# USBC.net
KiCad netlist of a schematic drawn in Altium Designer
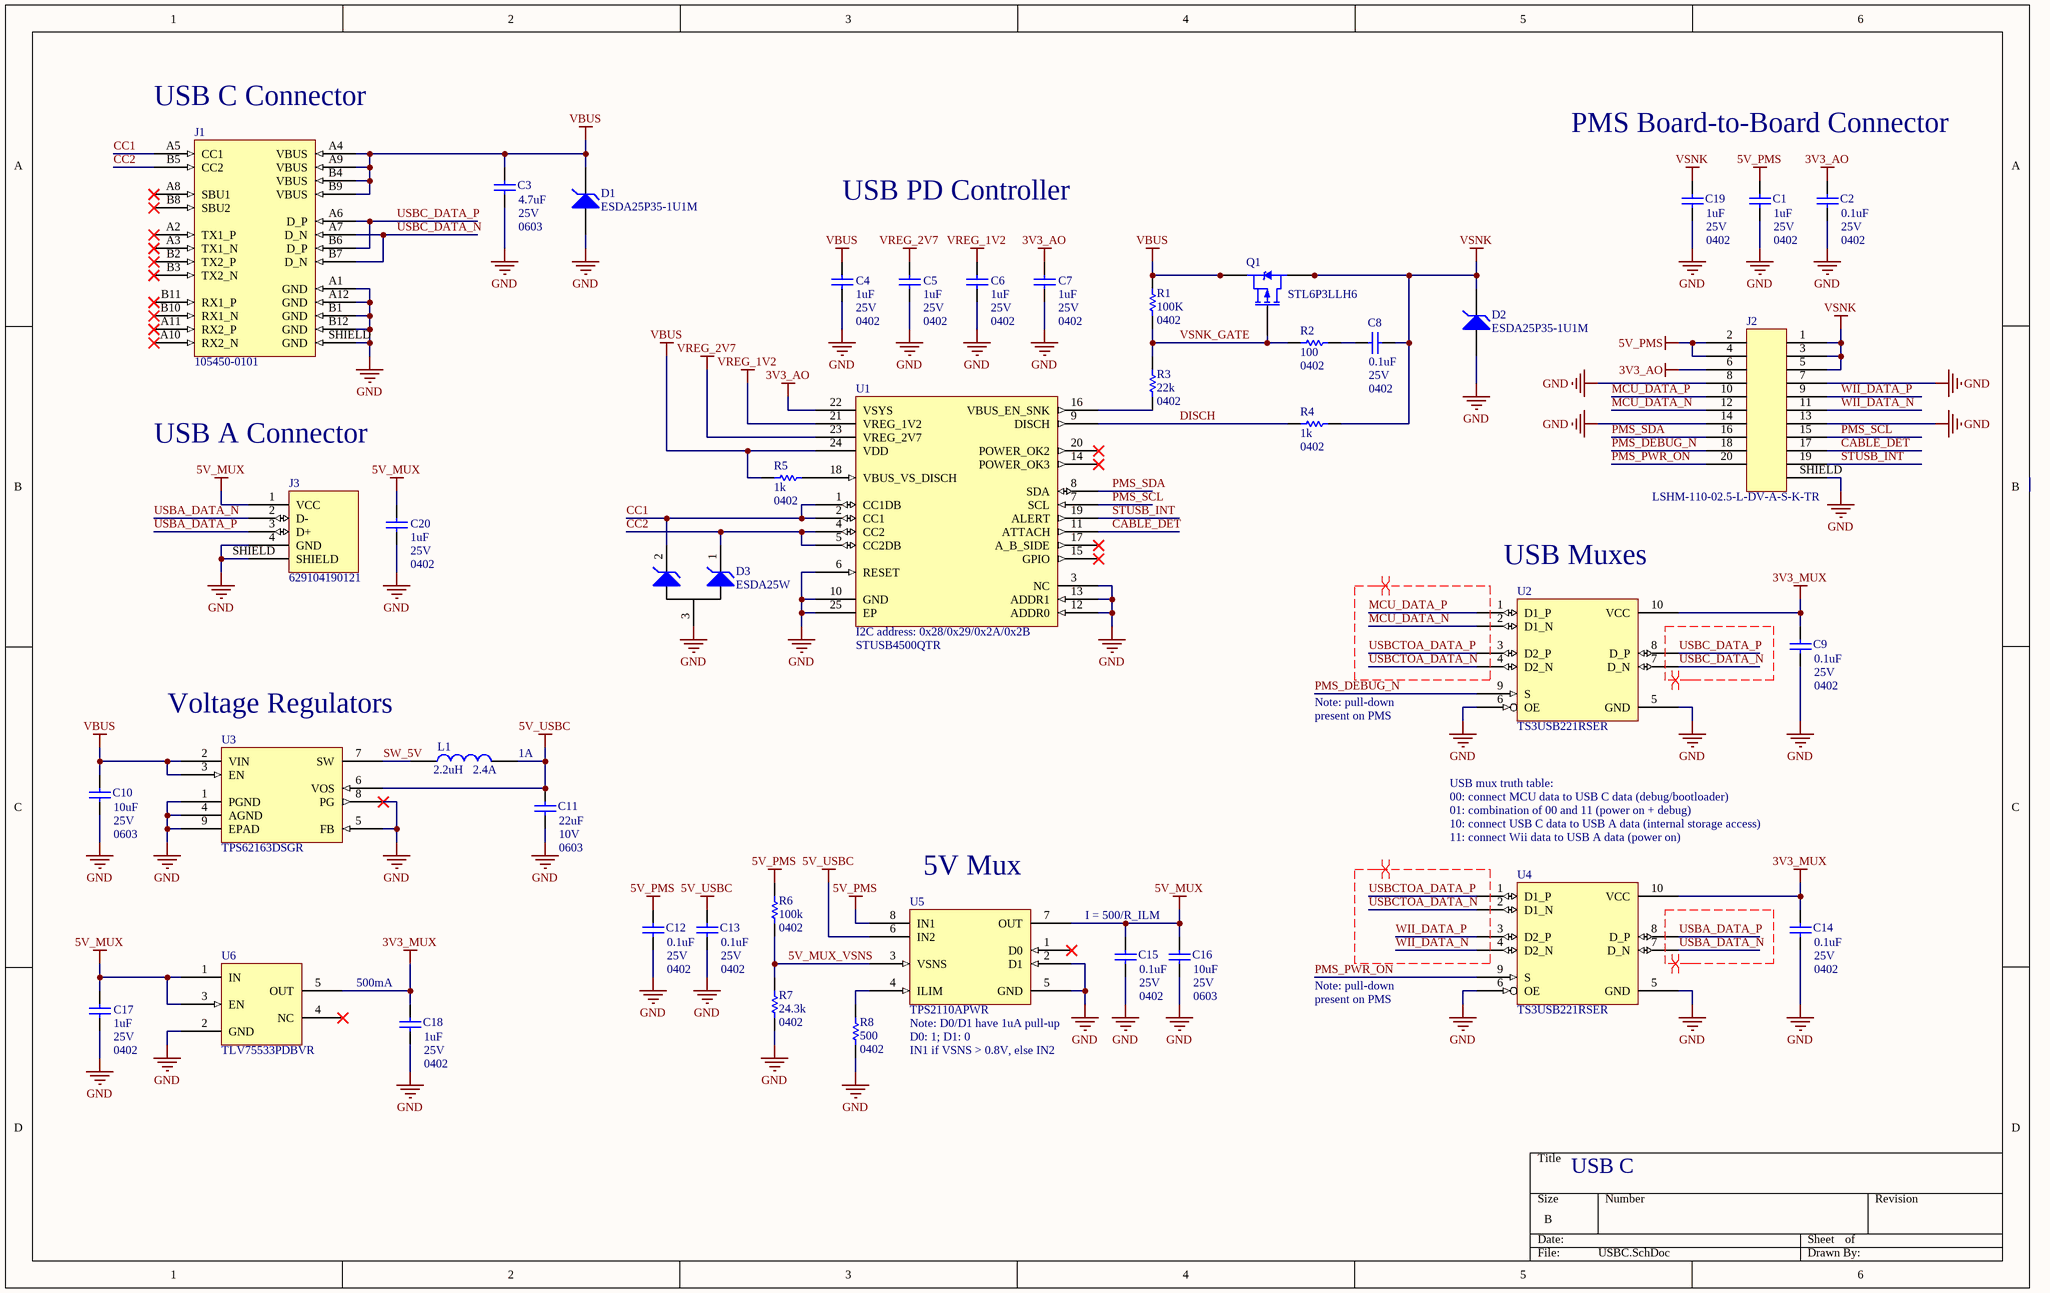
[diagram p0: USBC.SchDoc]

(export (version "E")
  (design (tool "Eeschema 10.0.6"))
  (components
    (comp (ref "C1")
      (value "1uF")
      (footprint "CAPC1005X06N")
      (description "General purpose capacitor")
      (fields
        (field (name "RATED VOLTAGE") "25V")
        (field (name "PACKAGE") "0402")
        (field (name "Comment") "Capacitor")
      )
      (libsource (lib "Schematic_Generic") (part "Capacitor"))
    )
    (comp (ref "C2")
      (value "0.1uF")
      (footprint "CAPC1005X06N")
      (description "General purpose capacitor")
      (fields
        (field (name "RATED VOLTAGE") "25V")
        (field (name "PACKAGE") "0402")
        (field (name "Comment") "Capacitor")
      )
      (libsource (lib "Schematic_Generic") (part "Capacitor"))
    )
    (comp (ref "C3")
      (value "4.7uF")
      (footprint "CAPC1608X09N")
      (description "General purpose capacitor")
      (fields
        (field (name "RATED VOLTAGE") "25V")
        (field (name "PACKAGE") "0603")
        (field (name "Comment") "Capacitor")
      )
      (libsource (lib "Schematic_Generic") (part "Capacitor"))
    )
    (comp (ref "C4")
      (value "1uF")
      (footprint "CAPC1005X06N")
      (description "General purpose capacitor")
      (fields
        (field (name "RATED VOLTAGE") "25V")
        (field (name "PACKAGE") "0402")
        (field (name "Comment") "Capacitor")
      )
      (libsource (lib "Schematic_Generic") (part "Capacitor"))
    )
    (comp (ref "C5")
      (value "1uF")
      (footprint "CAPC1005X06N")
      (description "General purpose capacitor")
      (fields
        (field (name "RATED VOLTAGE") "25V")
        (field (name "PACKAGE") "0402")
        (field (name "Comment") "Capacitor")
      )
      (libsource (lib "Schematic_Generic") (part "Capacitor"))
    )
    (comp (ref "C6")
      (value "1uF")
      (footprint "CAPC1005X06N")
      (description "General purpose capacitor")
      (fields
        (field (name "RATED VOLTAGE") "25V")
        (field (name "PACKAGE") "0402")
        (field (name "Comment") "Capacitor")
      )
      (libsource (lib "Schematic_Generic") (part "Capacitor"))
    )
    (comp (ref "C7")
      (value "1uF")
      (footprint "CAPC1005X06N")
      (description "General purpose capacitor")
      (fields
        (field (name "RATED VOLTAGE") "25V")
        (field (name "PACKAGE") "0402")
        (field (name "Comment") "Capacitor")
      )
      (libsource (lib "Schematic_Generic") (part "Capacitor"))
    )
    (comp (ref "C8")
      (value "0.1uF")
      (footprint "CAPC1005X06N")
      (description "General purpose capacitor")
      (fields
        (field (name "RATED VOLTAGE") "25V")
        (field (name "PACKAGE") "0402")
        (field (name "Comment") "Capacitor")
      )
      (libsource (lib "Schematic_Generic") (part "Capacitor"))
    )
    (comp (ref "C9")
      (value "0.1uF")
      (footprint "CAPC1005X06N")
      (description "General purpose capacitor")
      (fields
        (field (name "RATED VOLTAGE") "25V")
        (field (name "PACKAGE") "0402")
        (field (name "Comment") "Capacitor")
      )
      (libsource (lib "Schematic_Generic") (part "Capacitor"))
    )
    (comp (ref "C10")
      (value "10uF")
      (footprint "CAPC1608X09N")
      (description "General purpose capacitor")
      (fields
        (field (name "RATED VOLTAGE") "25V")
        (field (name "PACKAGE") "0603")
        (field (name "Comment") "Capacitor")
      )
      (libsource (lib "Schematic_Generic") (part "Capacitor"))
    )
    (comp (ref "C11")
      (value "22uF")
      (footprint "CAPC1608X09N")
      (description "General purpose capacitor")
      (fields
        (field (name "RATED VOLTAGE") "10V")
        (field (name "PACKAGE") "0603")
        (field (name "Comment") "Capacitor")
      )
      (libsource (lib "Schematic_Generic") (part "Capacitor"))
    )
    (comp (ref "C12")
      (value "0.1uF")
      (footprint "CAPC1005X06N")
      (description "General purpose capacitor")
      (fields
        (field (name "RATED VOLTAGE") "25V")
        (field (name "PACKAGE") "0402")
        (field (name "Comment") "Capacitor")
      )
      (libsource (lib "Schematic_Generic") (part "Capacitor"))
    )
    (comp (ref "C13")
      (value "0.1uF")
      (footprint "CAPC1005X06N")
      (description "General purpose capacitor")
      (fields
        (field (name "RATED VOLTAGE") "25V")
        (field (name "PACKAGE") "0402")
        (field (name "Comment") "Capacitor")
      )
      (libsource (lib "Schematic_Generic") (part "Capacitor"))
    )
    (comp (ref "C14")
      (value "0.1uF")
      (footprint "CAPC1005X06N")
      (description "General purpose capacitor")
      (fields
        (field (name "RATED VOLTAGE") "25V")
        (field (name "PACKAGE") "0402")
        (field (name "Comment") "Capacitor")
      )
      (libsource (lib "Schematic_Generic") (part "Capacitor"))
    )
    (comp (ref "C15")
      (value "0.1uF")
      (footprint "CAPC1005X06N")
      (description "General purpose capacitor")
      (fields
        (field (name "RATED VOLTAGE") "25V")
        (field (name "PACKAGE") "0402")
        (field (name "Comment") "Capacitor")
      )
      (libsource (lib "Schematic_Generic") (part "Capacitor"))
    )
    (comp (ref "C16")
      (value "10uF")
      (footprint "CAPC1608X09N")
      (description "General purpose capacitor")
      (fields
        (field (name "RATED VOLTAGE") "25V")
        (field (name "PACKAGE") "0603")
        (field (name "Comment") "Capacitor")
      )
      (libsource (lib "Schematic_Generic") (part "Capacitor"))
    )
    (comp (ref "C17")
      (value "1uF")
      (footprint "CAPC1005X06N")
      (description "General purpose capacitor")
      (fields
        (field (name "RATED VOLTAGE") "25V")
        (field (name "PACKAGE") "0402")
        (field (name "Comment") "Capacitor")
      )
      (libsource (lib "Schematic_Generic") (part "Capacitor"))
    )
    (comp (ref "C18")
      (value "1uF")
      (footprint "CAPC1005X06N")
      (description "General purpose capacitor")
      (fields
        (field (name "RATED VOLTAGE") "25V")
        (field (name "PACKAGE") "0402")
        (field (name "Comment") "Capacitor")
      )
      (libsource (lib "Schematic_Generic") (part "Capacitor"))
    )
    (comp (ref "C19")
      (value "1uF")
      (footprint "CAPC1005X06N")
      (description "General purpose capacitor")
      (fields
        (field (name "RATED VOLTAGE") "25V")
        (field (name "PACKAGE") "0402")
        (field (name "Comment") "Capacitor")
      )
      (libsource (lib "Schematic_Generic") (part "Capacitor"))
    )
    (comp (ref "C20")
      (value "1uF")
      (footprint "CAPC1005X06N")
      (description "General purpose capacitor")
      (fields
        (field (name "RATED VOLTAGE") "25V")
        (field (name "PACKAGE") "0402")
        (field (name "Comment") "Capacitor")
      )
      (libsource (lib "Schematic_Generic") (part "Capacitor"))
    )
    (comp (ref "D1")
      (value "ESDA25P35-1U1M")
      (footprint "Footprint_Diode:DFN105P160X60-2N")
      (description "STMICROELECTRONICS - ESDA25P35-1U1M - ESD Protection Device, Unidirectional, 41 V, QFN, 2 Pins")
      (fields (field (name "MANUFACTURER") "STMicroelectronics"))
      (libsource (lib "Schematic_Diode") (part "ESDA25P35-1U1M"))
    )
    (comp (ref "D2")
      (value "ESDA25P35-1U1M")
      (footprint "Footprint_Diode:DFN105P160X60-2N")
      (description "STMICROELECTRONICS - ESDA25P35-1U1M - ESD Protection Device, Unidirectional, 41 V, QFN, 2 Pins")
      (fields (field (name "MANUFACTURER") "STMicroelectronics"))
      (libsource (lib "Schematic_Diode") (part "ESDA25P35-1U1M"))
    )
    (comp (ref "D3")
      (value "ESDA25W")
      (footprint "Footprint_Diode:SOT65P210X110-3N")
      (fields (field (name "MANUFACTURER") "STMicroelectronics"))
      (libsource (lib "Schematic_Diode") (part "ESDA25W"))
    )
    (comp (ref "J1")
      (value "105450-0101")
      (footprint "Footprint_Connector:1054500101")
      (description "USB Shielded I/O Receptacle; Type C; Right Angle; Surface Mount; Gold over Nickel")
      (fields (field (name "MANUFACTURER") "Molex"))
      (libsource (lib "Schematic_Connector") (part "105450-0101"))
    )
    (comp (ref "J2")
      (value "LSHM-110-02.5-L-DV-A-S-K-TR")
      (footprint "Footprint_Connector:LSHM-110-02.5-L-DV-A-S")
      (description "HERMAPHRODITIC 0.50MM SMD 20POS 2.5MM")
      (fields (field (name "MANUFACTURER") "Samtec"))
      (libsource (lib "Schematic_Connector") (part "LSHM-110-02.5-L-DV-A-S-K-TR"))
    )
    (comp (ref "J3")
      (value "629104190121")
      (footprint "Footprint_Connector:629104190121")
      (fields (field (name "MANUFACTURER") "Wurth Electronics"))
      (libsource (lib "Schematic_Connector") (part "629104190121"))
    )
    (comp (ref "L1")
      (value "CIGT252010EH2R2MNE")
      (footprint "Footprint_Inductor:INDC2520X10N")
      (description "FIXED IND 2.2UH 2.4A 80MOHM SMD")
      (fields
        (field (name "MANUFACTURER") "Samsung")
        (field (name "TOLERANCE") "20%")
        (field (name "CURRENT RATING") "2.4A")
        (field (name "INDUCTANCE") "2.2uH")
      )
      (libsource (lib "Schematic_Inductor") (part "CIGT252010EH2R2MNE"))
    )
    (comp (ref "Q1")
      (value "STL6P3LLH6")
      (footprint "Footprint_Transistor:QFN0P315X300X90-10N")
      (description "MOSFET POWER MOSFET")
      (fields (field (name "MANUFACTURER") "STMicroelectronics"))
      (libsource (lib "Schematic_Transistor") (part "STL6P3LLH6"))
    )
    (comp (ref "R1")
      (value "100K")
      (footprint "RESC1005X04N")
      (description "General purpose resistor")
      (fields (field (name "PACKAGE") "0402") (field (name "Comment") "Resistor"))
      (libsource (lib "Schematic_Generic") (part "Resistor"))
    )
    (comp (ref "R2")
      (value "100")
      (footprint "RESC1005X04N")
      (description "General purpose resistor")
      (fields (field (name "PACKAGE") "0402") (field (name "Comment") "Resistor"))
      (libsource (lib "Schematic_Generic") (part "Resistor"))
    )
    (comp (ref "R3")
      (value "22k")
      (footprint "RESC1005X04N")
      (description "General purpose resistor")
      (fields (field (name "PACKAGE") "0402") (field (name "Comment") "Resistor"))
      (libsource (lib "Schematic_Generic") (part "Resistor"))
    )
    (comp (ref "R4")
      (value "1k")
      (footprint "RESC1005X04N")
      (description "General purpose resistor")
      (fields (field (name "PACKAGE") "0402") (field (name "Comment") "Resistor"))
      (libsource (lib "Schematic_Generic") (part "Resistor"))
    )
    (comp (ref "R5")
      (value "1k")
      (footprint "RESC1005X04N")
      (description "General purpose resistor")
      (fields (field (name "PACKAGE") "0402") (field (name "Comment") "Resistor"))
      (libsource (lib "Schematic_Generic") (part "Resistor"))
    )
    (comp (ref "R6")
      (value "100k")
      (footprint "RESC1005X04N")
      (description "General purpose resistor")
      (fields (field (name "PACKAGE") "0402") (field (name "Comment") "Resistor"))
      (libsource (lib "Schematic_Generic") (part "Resistor"))
    )
    (comp (ref "R7")
      (value "24.3k")
      (footprint "RESC1005X04N")
      (description "General purpose resistor")
      (fields (field (name "PACKAGE") "0402") (field (name "Comment") "Resistor"))
      (libsource (lib "Schematic_Generic") (part "Resistor"))
    )
    (comp (ref "R8")
      (value "500")
      (footprint "RESC1005X04N")
      (description "General purpose resistor")
      (fields (field (name "PACKAGE") "0402") (field (name "Comment") "Resistor"))
      (libsource (lib "Schematic_Generic") (part "Resistor"))
    )
    (comp (ref "U1")
      (value "STUSB4500QTR")
      (footprint "Footprint_IC:QFN50P400X400X100_HS-25N")
      (description "STAND-ALONE USB PD CONTROLLER (")
      (fields (field (name "MANUFACTURER") "STMicroelectronics"))
      (libsource (lib "Schematic_IC") (part "STUSB4500QTR"))
    )
    (comp (ref "U2")
      (value "TS3USB221RSER")
      (footprint "Footprint_IC:QFN50P150X200X60-10N")
      (description "TEXAS INSTRUMENTS         TS3USB221RSER.             USB SWITCH, 480MBPS, 1.1GHZ, QFN-10")
      (fields (field (name "MANUFACTURER") "Texas Instruments"))
      (libsource (lib "Schematic_IC") (part "TS3USB221RSER"))
    )
    (comp (ref "U3")
      (value "TPS62163DSGR")
      (footprint "Footprint_PMIC:SON50P200X80_HS-9N")
      (description "3V-17V 1A Step-Down Converters with DCS-Control? 8-WSON -40 to 125")
      (fields (field (name "MANUFACTURER") "Texas Instruments"))
      (libsource (lib "Schematic_PMIC") (part "TPS62163DSGR"))
    )
    (comp (ref "U4")
      (value "TS3USB221RSER")
      (footprint "Footprint_IC:QFN50P150X200X60-10N")
      (description "TEXAS INSTRUMENTS         TS3USB221RSER.             USB SWITCH, 480MBPS, 1.1GHZ, QFN-10")
      (fields (field (name "MANUFACTURER") "Texas Instruments"))
      (libsource (lib "Schematic_IC") (part "TS3USB221RSER"))
    )
    (comp (ref "U5")
      (value "TPS2110APWR")
      (footprint "Footprint_PMIC:TSOP65P640X120-8N")
      (description "IC OR CTRLR SRC SELECT 8TSSOP")
      (fields (field (name "MANUFACTURER") "Texas Instruments"))
      (libsource (lib "Schematic_PMIC") (part "TPS2110APWR"))
    )
    (comp (ref "U6")
      (value "TLV75533PDBVR")
      (footprint "Footprint_PMIC:SOT95P280X145-5N")
      (description "IC REG LINEAR 3.3V 500MA SOT23-5")
      (fields (field (name "MANUFACTURER") "Texas Instruments"))
      (libsource (lib "Schematic_PMIC") (part "TLV75533PDBVR"))
    )
  )
  (nets
    (net (code "1") (name "/5V_MUX_VSNS") (class "Default")
      (node (ref "R6") (pin "1") (pinfunction "1_1") (pintype "passive"))
      (node (ref "R7") (pin "2") (pinfunction "2_2") (pintype "passive"))
      (node (ref "U5") (pin "3") (pinfunction "VSNS_3") (pintype "input"))
    )
    (net (code "2") (name "/CABLE_DET") (class "Default")
      (node (ref "J2") (pin "17") (pintype "passive"))
      (node (ref "U1") (pin "11") (pinfunction "ATTACH_11") (pintype "output"))
    )
    (net (code "3") (name "/CC1") (class "Default")
      (node (ref "D3") (pin "2") (pinfunction "K2_2") (pintype "passive"))
      (node (ref "J1") (pin "A5") (pinfunction "CC1_A5") (pintype "input"))
      (node (ref "U1") (pin "1") (pinfunction "CC1DB_1") (pintype "bidirectional"))
      (node (ref "U1") (pin "2") (pinfunction "CC1_2") (pintype "bidirectional"))
    )
    (net (code "4") (name "/CC2") (class "Default")
      (node (ref "D3") (pin "1") (pinfunction "K1_1") (pintype "passive"))
      (node (ref "J1") (pin "B5") (pinfunction "CC2_B5") (pintype "input"))
      (node (ref "U1") (pin "4") (pinfunction "CC2_4") (pintype "bidirectional"))
      (node (ref "U1") (pin "5") (pinfunction "CC2DB_5") (pintype "bidirectional"))
    )
    (net (code "5") (name "/DISCH") (class "Default")
      (node (ref "R4") (pin "2") (pinfunction "2_2") (pintype "passive"))
      (node (ref "U1") (pin "9") (pinfunction "DISCH_9") (pintype "output"))
    )
    (net (code "6") (name "/MCU_DATA_N") (class "Default")
      (node (ref "J2") (pin "12") (pintype "passive"))
      (node (ref "U2") (pin "2") (pinfunction "D1_N_2") (pintype "bidirectional"))
    )
    (net (code "7") (name "/MCU_DATA_P") (class "Default")
      (node (ref "J2") (pin "10") (pintype "passive"))
      (node (ref "U2") (pin "1") (pinfunction "D1_P_1") (pintype "bidirectional"))
    )
    (net (code "8") (name "/PMS_DEBUG_N") (class "Default")
      (node (ref "J2") (pin "18") (pintype "passive"))
      (node (ref "U2") (pin "9") (pinfunction "S_9") (pintype "input"))
    )
    (net (code "9") (name "/PMS_PWR_ON") (class "Default")
      (node (ref "J2") (pin "20") (pintype "passive"))
      (node (ref "U4") (pin "9") (pinfunction "S_9") (pintype "input"))
    )
    (net (code "10") (name "/PMS_SCL") (class "Default")
      (node (ref "J2") (pin "15") (pintype "passive"))
      (node (ref "U1") (pin "7") (pinfunction "SCL_7") (pintype "input"))
    )
    (net (code "11") (name "/PMS_SDA") (class "Default")
      (node (ref "J2") (pin "16") (pintype "passive"))
      (node (ref "U1") (pin "8") (pinfunction "SDA_8") (pintype "bidirectional"))
    )
    (net (code "12") (name "/STUSB_INT") (class "Default")
      (node (ref "J2") (pin "19") (pintype "passive"))
      (node (ref "U1") (pin "19") (pinfunction "ALERT_19") (pintype "output"))
    )
    (net (code "13") (name "/SW_5V") (class "Default")
      (node (ref "L1") (pin "1") (pinfunction "1_1") (pintype "passive"))
      (node (ref "U3") (pin "7") (pinfunction "SW_7") (pintype "power_in"))
    )
    (net (code "14") (name "/USBA_DATA_N") (class "Default")
      (node (ref "J3") (pin "2") (pinfunction "D-_2") (pintype "bidirectional"))
      (node (ref "U4") (pin "7") (pinfunction "D_N_7") (pintype "bidirectional"))
    )
    (net (code "15") (name "/USBA_DATA_P") (class "Default")
      (node (ref "J3") (pin "3") (pinfunction "D+_3") (pintype "bidirectional"))
      (node (ref "U4") (pin "8") (pinfunction "D_P_8") (pintype "bidirectional"))
    )
    (net (code "16") (name "/USBCTOA_DATA_N") (class "Default")
      (node (ref "U2") (pin "4") (pinfunction "D2_N_4") (pintype "bidirectional"))
      (node (ref "U4") (pin "2") (pinfunction "D1_N_2") (pintype "bidirectional"))
    )
    (net (code "17") (name "/USBCTOA_DATA_P") (class "Default")
      (node (ref "U2") (pin "3") (pinfunction "D2_P_3") (pintype "bidirectional"))
      (node (ref "U4") (pin "1") (pinfunction "D1_P_1") (pintype "bidirectional"))
    )
    (net (code "18") (name "/USBC_DATA_N") (class "Default")
      (node (ref "J1") (pin "A7") (pinfunction "D_N_A7") (pintype "input"))
      (node (ref "J1") (pin "B7") (pinfunction "D_N_B7") (pintype "input"))
      (node (ref "U2") (pin "7") (pinfunction "D_N_7") (pintype "bidirectional"))
    )
    (net (code "19") (name "/USBC_DATA_P") (class "Default")
      (node (ref "J1") (pin "A6") (pinfunction "D_P_A6") (pintype "input"))
      (node (ref "J1") (pin "B6") (pinfunction "D_P_B6") (pintype "input"))
      (node (ref "U2") (pin "8") (pinfunction "D_P_8") (pintype "bidirectional"))
    )
    (net (code "20") (name "/VSNK_GATE") (class "Default")
      (node (ref "Q1") (pin "4") (pinfunction "G_4") (pintype "passive"))
      (node (ref "R1") (pin "1") (pinfunction "1_1") (pintype "passive"))
      (node (ref "R2") (pin "2") (pinfunction "2_2") (pintype "passive"))
      (node (ref "R3") (pin "2") (pinfunction "2_2") (pintype "passive"))
    )
    (net (code "21") (name "/WII_DATA_N") (class "Default")
      (node (ref "J2") (pin "11") (pintype "passive"))
      (node (ref "U4") (pin "4") (pinfunction "D2_N_4") (pintype "bidirectional"))
    )
    (net (code "22") (name "/WII_DATA_P") (class "Default")
      (node (ref "J2") (pin "9") (pintype "passive"))
      (node (ref "U4") (pin "3") (pinfunction "D2_P_3") (pintype "bidirectional"))
    )
    (net (code "23") (name "3V3_AO") (class "Default")
      (node (ref "C2") (pin "2") (pinfunction "2_2") (pintype "passive"))
      (node (ref "C7") (pin "2") (pinfunction "2_2") (pintype "passive"))
      (node (ref "J2") (pin "6") (pintype "passive"))
      (node (ref "U1") (pin "22") (pinfunction "VSYS_22") (pintype "power_in"))
    )
    (net (code "24") (name "3V3_MUX") (class "Default")
      (node (ref "C14") (pin "2") (pinfunction "2_2") (pintype "passive"))
      (node (ref "C18") (pin "2") (pinfunction "2_2") (pintype "passive"))
      (node (ref "C9") (pin "2") (pinfunction "2_2") (pintype "passive"))
      (node (ref "U2") (pin "10") (pinfunction "VCC_10") (pintype "power_in"))
      (node (ref "U4") (pin "10") (pinfunction "VCC_10") (pintype "power_in"))
      (node (ref "U6") (pin "5") (pinfunction "OUT_5") (pintype "power_in"))
    )
    (net (code "25") (name "5V_MUX") (class "Default")
      (node (ref "C15") (pin "2") (pinfunction "2_2") (pintype "passive"))
      (node (ref "C16") (pin "2") (pinfunction "2_2") (pintype "passive"))
      (node (ref "C17") (pin "2") (pinfunction "2_2") (pintype "passive"))
      (node (ref "C20") (pin "2") (pinfunction "2_2") (pintype "passive"))
      (node (ref "J3") (pin "1") (pinfunction "VCC_1") (pintype "power_in"))
      (node (ref "U5") (pin "7") (pinfunction "OUT_7") (pintype "power_in"))
      (node (ref "U6") (pin "1") (pinfunction "IN_1") (pintype "power_in"))
      (node (ref "U6") (pin "3") (pinfunction "EN_3") (pintype "input"))
    )
    (net (code "26") (name "5V_PMS") (class "Default")
      (node (ref "C1") (pin "2") (pinfunction "2_2") (pintype "passive"))
      (node (ref "C12") (pin "2") (pinfunction "2_2") (pintype "passive"))
      (node (ref "J2") (pin "2") (pintype "passive"))
      (node (ref "J2") (pin "4") (pintype "passive"))
      (node (ref "R6") (pin "2") (pinfunction "2_2") (pintype "passive"))
      (node (ref "U5") (pin "8") (pinfunction "IN1_8") (pintype "power_in"))
    )
    (net (code "27") (name "5V_USBC") (class "Default")
      (node (ref "C11") (pin "2") (pinfunction "2_2") (pintype "passive"))
      (node (ref "C13") (pin "2") (pinfunction "2_2") (pintype "passive"))
      (node (ref "L1") (pin "2") (pinfunction "2_2") (pintype "passive"))
      (node (ref "U3") (pin "6") (pinfunction "VOS_6") (pintype "input"))
      (node (ref "U5") (pin "6") (pinfunction "IN2_6") (pintype "power_in"))
    )
    (net (code "28") (name "GND") (class "Default")
      (node (ref "C1") (pin "1") (pinfunction "1_1") (pintype "passive"))
      (node (ref "C10") (pin "1") (pinfunction "1_1") (pintype "passive"))
      (node (ref "C11") (pin "1") (pinfunction "1_1") (pintype "passive"))
      (node (ref "C12") (pin "1") (pinfunction "1_1") (pintype "passive"))
      (node (ref "C13") (pin "1") (pinfunction "1_1") (pintype "passive"))
      (node (ref "C14") (pin "1") (pinfunction "1_1") (pintype "passive"))
      (node (ref "C15") (pin "1") (pinfunction "1_1") (pintype "passive"))
      (node (ref "C16") (pin "1") (pinfunction "1_1") (pintype "passive"))
      (node (ref "C17") (pin "1") (pinfunction "1_1") (pintype "passive"))
      (node (ref "C18") (pin "1") (pinfunction "1_1") (pintype "passive"))
      (node (ref "C19") (pin "1") (pinfunction "1_1") (pintype "passive"))
      (node (ref "C2") (pin "1") (pinfunction "1_1") (pintype "passive"))
      (node (ref "C20") (pin "1") (pinfunction "1_1") (pintype "passive"))
      (node (ref "C3") (pin "1") (pinfunction "1_1") (pintype "passive"))
      (node (ref "C4") (pin "1") (pinfunction "1_1") (pintype "passive"))
      (node (ref "C5") (pin "1") (pinfunction "1_1") (pintype "passive"))
      (node (ref "C6") (pin "1") (pinfunction "1_1") (pintype "passive"))
      (node (ref "C7") (pin "1") (pinfunction "1_1") (pintype "passive"))
      (node (ref "C9") (pin "1") (pinfunction "1_1") (pintype "passive"))
      (node (ref "D1") (pin "2") (pinfunction "A_2") (pintype "passive"))
      (node (ref "D2") (pin "2") (pinfunction "A_2") (pintype "passive"))
      (node (ref "D3") (pin "3") (pinfunction "A_3") (pintype "passive"))
      (node (ref "J1") (pin "A1") (pinfunction "GND_A1") (pintype "input"))
      (node (ref "J1") (pin "A12") (pinfunction "GND_A12") (pintype "input"))
      (node (ref "J1") (pin "B1") (pinfunction "GND_B1") (pintype "input"))
      (node (ref "J1") (pin "B12") (pinfunction "GND_B12") (pintype "input"))
      (node (ref "J1") (pin "SHIELD") (pinfunction "GND_SHIELD") (pintype "input"))
      (node (ref "J2") (pin "13") (pintype "passive"))
      (node (ref "J2") (pin "14") (pintype "passive"))
      (node (ref "J2") (pin "7") (pintype "passive"))
      (node (ref "J2") (pin "8") (pintype "passive"))
      (node (ref "J2") (pin "SHIELD") (pintype "passive"))
      (node (ref "J3") (pin "4") (pinfunction "GND_4") (pintype "power_in"))
      (node (ref "J3") (pin "SHIELD") (pinfunction "SHIELD_SHIELD") (pintype "passive"))
      (node (ref "R7") (pin "1") (pinfunction "1_1") (pintype "passive"))
      (node (ref "R8") (pin "1") (pinfunction "1_1") (pintype "passive"))
      (node (ref "U1") (pin "10") (pinfunction "GND_10") (pintype "power_in"))
      (node (ref "U1") (pin "12") (pinfunction "ADDR0_12") (pintype "input"))
      (node (ref "U1") (pin "13") (pinfunction "ADDR1_13") (pintype "input"))
      (node (ref "U1") (pin "25") (pinfunction "EP_25") (pintype "passive"))
      (node (ref "U1") (pin "3") (pinfunction "NC_3") (pintype "passive"))
      (node (ref "U1") (pin "6") (pinfunction "RESET_6") (pintype "input"))
      (node (ref "U2") (pin "5") (pinfunction "GND_5") (pintype "power_in"))
      (node (ref "U2") (pin "6") (pinfunction "OE_6") (pintype "input"))
      (node (ref "U3") (pin "1") (pinfunction "PGND_1") (pintype "power_in"))
      (node (ref "U3") (pin "4") (pinfunction "AGND_4") (pintype "power_in"))
      (node (ref "U3") (pin "5") (pinfunction "FB_5") (pintype "input"))
      (node (ref "U3") (pin "8") (pinfunction "PG_8") (pintype "output"))
      (node (ref "U3") (pin "9") (pinfunction "EPAD_9") (pintype "passive"))
      (node (ref "U4") (pin "5") (pinfunction "GND_5") (pintype "power_in"))
      (node (ref "U4") (pin "6") (pinfunction "OE_6") (pintype "input"))
      (node (ref "U5") (pin "2") (pinfunction "D1_2") (pintype "input"))
      (node (ref "U5") (pin "5") (pinfunction "GND_5") (pintype "power_in"))
      (node (ref "U6") (pin "2") (pinfunction "GND_2") (pintype "power_in"))
    )
    (net (code "29") (name "Net-(C8-Pad2)") (class "Default")
      (node (ref "C8") (pin "2") (pinfunction "2_2") (pintype "passive"))
      (node (ref "R2") (pin "1") (pinfunction "1_1") (pintype "passive"))
    )
    (net (code "30") (name "Net-(U1-VBUS_EN_SNK)") (class "Default")
      (node (ref "R3") (pin "1") (pinfunction "1_1") (pintype "passive"))
      (node (ref "U1") (pin "16") (pinfunction "VBUS_EN_SNK_16") (pintype "output"))
    )
    (net (code "31") (name "Net-(U1-VBUS_VS_DISCH)") (class "Default")
      (node (ref "R5") (pin "1") (pinfunction "1_1") (pintype "passive"))
      (node (ref "U1") (pin "18") (pinfunction "VBUS_VS_DISCH_18") (pintype "input"))
    )
    (net (code "32") (name "Net-(U5-ILIM)") (class "Default")
      (node (ref "R8") (pin "2") (pinfunction "2_2") (pintype "passive"))
      (node (ref "U5") (pin "4") (pinfunction "ILIM_4") (pintype "input"))
    )
    (net (code "33") (name "VBUS") (class "Default")
      (node (ref "C10") (pin "2") (pinfunction "2_2") (pintype "passive"))
      (node (ref "C3") (pin "2") (pinfunction "2_2") (pintype "passive"))
      (node (ref "C4") (pin "2") (pinfunction "2_2") (pintype "passive"))
      (node (ref "D1") (pin "1") (pinfunction "K_1") (pintype "passive"))
      (node (ref "J1") (pin "A4") (pinfunction "VBUS_A4") (pintype "input"))
      (node (ref "J1") (pin "A9") (pinfunction "VBUS_A9") (pintype "input"))
      (node (ref "J1") (pin "B4") (pinfunction "VBUS_B4") (pintype "input"))
      (node (ref "J1") (pin "B9") (pinfunction "VBUS_B9") (pintype "input"))
      (node (ref "Q1") (pin "1") (pinfunction "S_1") (pintype "passive"))
      (node (ref "Q1") (pin "2") (pinfunction "S_2") (pintype "passive"))
      (node (ref "Q1") (pin "3") (pinfunction "S_3") (pintype "passive"))
      (node (ref "R1") (pin "2") (pinfunction "2_2") (pintype "passive"))
      (node (ref "R5") (pin "2") (pinfunction "2_2") (pintype "passive"))
      (node (ref "U1") (pin "24") (pinfunction "VDD_24") (pintype "power_in"))
      (node (ref "U3") (pin "2") (pinfunction "VIN_2") (pintype "power_in"))
      (node (ref "U3") (pin "3") (pinfunction "EN_3") (pintype "input"))
    )
    (net (code "34") (name "VREG_1V2") (class "Default")
      (node (ref "C6") (pin "2") (pinfunction "2_2") (pintype "passive"))
      (node (ref "U1") (pin "21") (pinfunction "VREG_1V2_21") (pintype "power_in"))
    )
    (net (code "35") (name "VREG_2V7") (class "Default")
      (node (ref "C5") (pin "2") (pinfunction "2_2") (pintype "passive"))
      (node (ref "U1") (pin "23") (pinfunction "VREG_2V7_23") (pintype "power_in"))
    )
    (net (code "36") (name "VSNK") (class "Default")
      (node (ref "C19") (pin "2") (pinfunction "2_2") (pintype "passive"))
      (node (ref "C8") (pin "1") (pinfunction "1_1") (pintype "passive"))
      (node (ref "D2") (pin "1") (pinfunction "K_1") (pintype "passive"))
      (node (ref "J2") (pin "1") (pintype "passive"))
      (node (ref "J2") (pin "3") (pintype "passive"))
      (node (ref "J2") (pin "5") (pintype "passive"))
      (node (ref "Q1") (pin "5") (pinfunction "D_5") (pintype "passive"))
      (node (ref "Q1") (pin "6") (pinfunction "D_6") (pintype "passive"))
      (node (ref "Q1") (pin "7") (pinfunction "D_7") (pintype "passive"))
      (node (ref "Q1") (pin "8") (pinfunction "D_8") (pintype "passive"))
      (node (ref "R4") (pin "1") (pinfunction "1_1") (pintype "passive"))
    )
    (net (code "37") (name "unconnected-(J1-RX1_N-PadB10)") (class "Default")
      (node (ref "J1") (pin "B10") (pinfunction "RX1_N_B10") (pintype "input+no_connect"))
    )
    (net (code "38") (name "unconnected-(J1-RX1_P-PadB11)") (class "Default")
      (node (ref "J1") (pin "B11") (pinfunction "RX1_P_B11") (pintype "input+no_connect"))
    )
    (net (code "39") (name "unconnected-(J1-RX2_N-PadA10)") (class "Default")
      (node (ref "J1") (pin "A10") (pinfunction "RX2_N_A10") (pintype "input+no_connect"))
    )
    (net (code "40") (name "unconnected-(J1-RX2_P-PadA11)") (class "Default")
      (node (ref "J1") (pin "A11") (pinfunction "RX2_P_A11") (pintype "input+no_connect"))
    )
    (net (code "41") (name "unconnected-(J1-SBU1-PadA8)") (class "Default")
      (node (ref "J1") (pin "A8") (pinfunction "SBU1_A8") (pintype "input+no_connect"))
    )
    (net (code "42") (name "unconnected-(J1-SBU2-PadB8)") (class "Default")
      (node (ref "J1") (pin "B8") (pinfunction "SBU2_B8") (pintype "input+no_connect"))
    )
    (net (code "43") (name "unconnected-(J1-TX1_N-PadA3)") (class "Default")
      (node (ref "J1") (pin "A3") (pinfunction "TX1_N_A3") (pintype "input+no_connect"))
    )
    (net (code "44") (name "unconnected-(J1-TX1_P-PadA2)") (class "Default")
      (node (ref "J1") (pin "A2") (pinfunction "TX1_P_A2") (pintype "input+no_connect"))
    )
    (net (code "45") (name "unconnected-(J1-TX2_N-PadB3)") (class "Default")
      (node (ref "J1") (pin "B3") (pinfunction "TX2_N_B3") (pintype "input+no_connect"))
    )
    (net (code "46") (name "unconnected-(J1-TX2_P-PadB2)") (class "Default")
      (node (ref "J1") (pin "B2") (pinfunction "TX2_P_B2") (pintype "input+no_connect"))
    )
    (net (code "47") (name "unconnected-(U1-A_B_SIDE-Pad17)") (class "Default")
      (node (ref "U1") (pin "17") (pinfunction "A_B_SIDE_17") (pintype "output+no_connect"))
    )
    (net (code "48") (name "unconnected-(U1-GPIO-Pad15)") (class "Default")
      (node (ref "U1") (pin "15") (pinfunction "GPIO_15") (pintype "output+no_connect"))
    )
    (net (code "49") (name "unconnected-(U1-POWER_OK2-Pad20)") (class "Default")
      (node (ref "U1") (pin "20") (pinfunction "POWER_OK2_20") (pintype "output+no_connect"))
    )
    (net (code "50") (name "unconnected-(U1-POWER_OK3-Pad14)") (class "Default")
      (node (ref "U1") (pin "14") (pinfunction "POWER_OK3_14") (pintype "output+no_connect"))
    )
    (net (code "51") (name "unconnected-(U5-D0-Pad1)") (class "Default")
      (node (ref "U5") (pin "1") (pinfunction "D0_1") (pintype "input+no_connect"))
    )
    (net (code "52") (name "unconnected-(U6-NC-Pad4)") (class "Default")
      (node (ref "U6") (pin "4") (pinfunction "NC_4") (pintype "passive+no_connect"))
    )
  )
)
